# WiFi_RGB_Lights.net
KiCad netlist of a schematic drawn in EAGLE
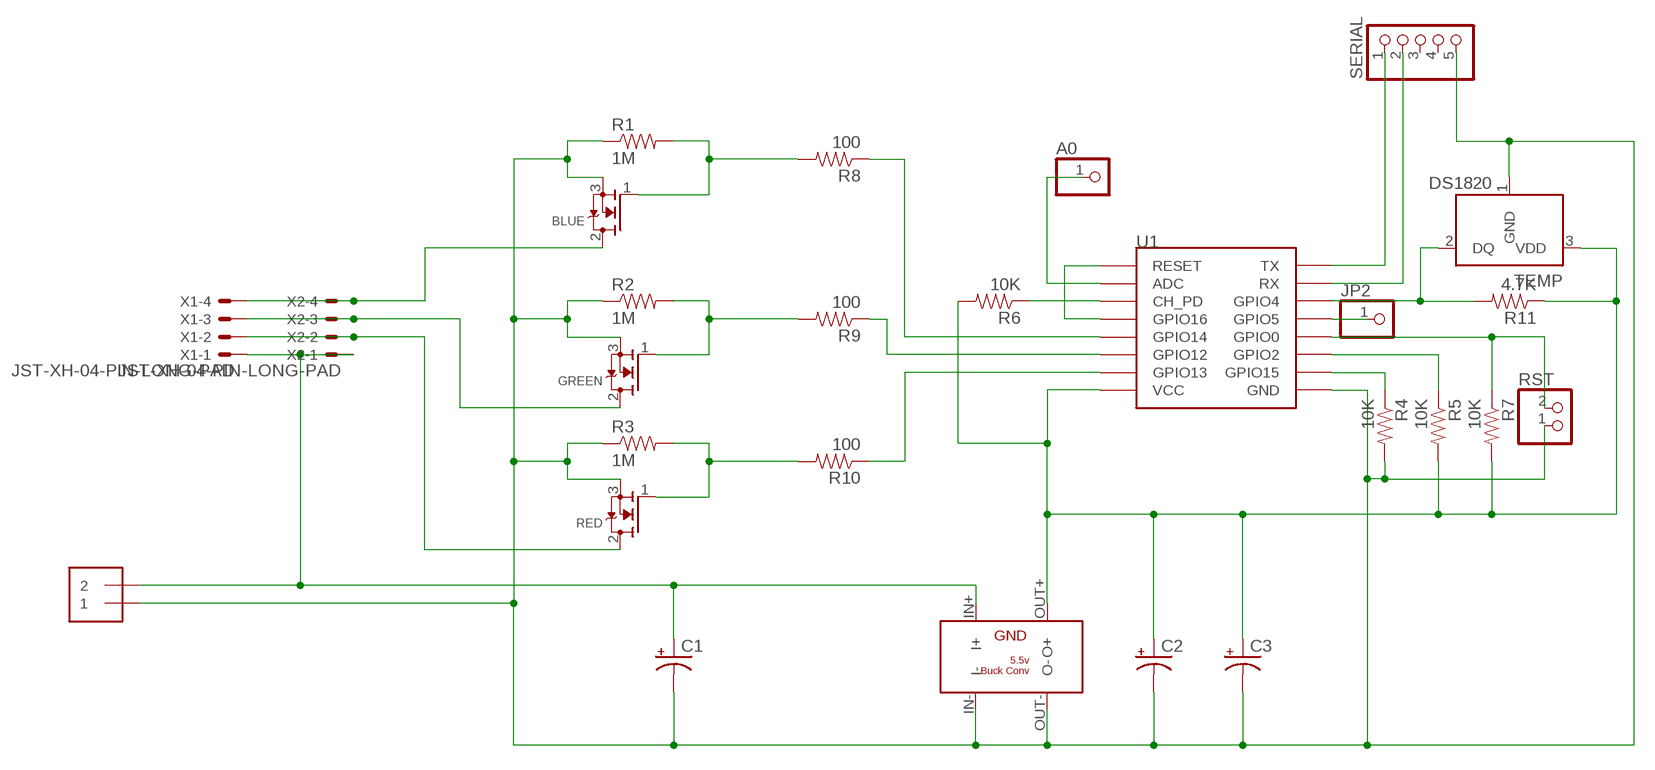
[diagram p0: schematic, sheet 1]

(export (version "E")
  (design (tool "Eeschema 10.0.6"))
  (components
    (comp (ref "3.3V")
      (value "BUCK_CONV_5.5V")
      (footprint "eagle-import:BUCK_CONV")
      (libsource (lib "eagle-import") (part "BUCK_CONV_5.5V"))
    )
    (comp (ref "A0")
      (value "PINHD-1X1")
      (footprint "eagle-import:1X01")
      (libsource (lib "eagle-import") (part "PINHD-1X1"))
    )
    (comp (ref "BLUE")
      (value "MOSFET-NGDS_TO220V")
      (footprint "eagle-import:TO220V")
      (libsource (lib "eagle-import") (part "MOSFET-NGDS_TO220V"))
    )
    (comp (ref "C1")
      (value "CPOL-USE5-8.5")
      (footprint "eagle-import:E5-8,5")
      (libsource (lib "eagle-import") (part "CPOL-USE5-8.5"))
    )
    (comp (ref "C2")
      (value "CPOL-USE2.5-6")
      (footprint "eagle-import:E2,5-6")
      (libsource (lib "eagle-import") (part "CPOL-USE2.5-6"))
    )
    (comp (ref "C3")
      (value "CPOL-USE2.5-6")
      (footprint "eagle-import:E2,5-6")
      (libsource (lib "eagle-import") (part "CPOL-USE2.5-6"))
    )
    (comp (ref "GREEN")
      (value "MOSFET-NGDS_TO220V")
      (footprint "eagle-import:TO220V")
      (libsource (lib "eagle-import") (part "MOSFET-NGDS_TO220V"))
    )
    (comp (ref "JP2")
      (value "PINHD-1X1")
      (footprint "eagle-import:1X01")
      (libsource (lib "eagle-import") (part "PINHD-1X1"))
    )
    (comp (ref "PWR")
      (value "5MM_TERMINAL_BLOCK")
      (footprint "eagle-import:5MM_TERMINAL_BLOCK")
      (libsource (lib "eagle-import") (part "5MM_TERMINAL_BLOCK"))
    )
    (comp (ref "R1")
      (value "1M")
      (footprint "eagle-import:1206")
      (libsource (lib "eagle-import") (part "RESISTOR1206"))
    )
    (comp (ref "R2")
      (value "1M")
      (footprint "eagle-import:1206")
      (libsource (lib "eagle-import") (part "RESISTOR1206"))
    )
    (comp (ref "R3")
      (value "1M")
      (footprint "eagle-import:1206")
      (libsource (lib "eagle-import") (part "RESISTOR1206"))
    )
    (comp (ref "R4")
      (value "10K")
      (footprint "eagle-import:1206")
      (libsource (lib "eagle-import") (part "RESISTOR1206"))
    )
    (comp (ref "R5")
      (value "10K")
      (footprint "eagle-import:1206")
      (libsource (lib "eagle-import") (part "RESISTOR1206"))
    )
    (comp (ref "R6")
      (value "10K")
      (footprint "eagle-import:1206")
      (libsource (lib "eagle-import") (part "RESISTOR1206"))
    )
    (comp (ref "R7")
      (value "10K")
      (footprint "eagle-import:1206")
      (libsource (lib "eagle-import") (part "RESISTOR1206"))
    )
    (comp (ref "R8")
      (value "100")
      (footprint "eagle-import:0805")
      (libsource (lib "eagle-import") (part "RESISTOR0805-RES"))
    )
    (comp (ref "R9")
      (value "100")
      (footprint "eagle-import:0805")
      (libsource (lib "eagle-import") (part "RESISTOR0805-RES"))
    )
    (comp (ref "R10")
      (value "100")
      (footprint "eagle-import:0805")
      (libsource (lib "eagle-import") (part "RESISTOR0805-RES"))
    )
    (comp (ref "R11")
      (value "4.7K")
      (footprint "eagle-import:1206")
      (libsource (lib "eagle-import") (part "RESISTOR1206"))
    )
    (comp (ref "RED")
      (value "MOSFET-NGDS_TO220V")
      (footprint "eagle-import:TO220V")
      (libsource (lib "eagle-import") (part "MOSFET-NGDS_TO220V"))
    )
    (comp (ref "RST")
      (value "JST_2PIN-THM")
      (footprint "eagle-import:JST-PH-2-THM")
      (libsource (lib "eagle-import") (part "JST_2PIN-THM"))
    )
    (comp (ref "SERIAL")
      (value "PINHD-1X5")
      (footprint "eagle-import:1X05")
      (libsource (lib "eagle-import") (part "PINHD-1X5"))
    )
    (comp (ref "TEMP")
      (value "DS1820")
      (footprint "eagle-import:TO-92")
      (libsource (lib "eagle-import") (part "DS1820"))
    )
    (comp (ref "U1")
      (value "ESP12")
      (footprint "eagle-import:ESP12")
      (libsource (lib "eagle-import") (part "ESP12"))
    )
    (comp (ref "X1")
      (value "JST-XH-04-PIN-LONG-PAD")
      (footprint "eagle-import:JST-XH-04-PACKAGE-LONG-PAD")
      (libsource (lib "eagle-import") (part "JST-XH-04-PIN-LONG-PAD"))
    )
    (comp (ref "X2")
      (value "JST-XH-04-PIN-LONG-PAD")
      (footprint "eagle-import:JST-XH-04-PACKAGE-LONG-PAD")
      (libsource (lib "eagle-import") (part "JST-XH-04-PIN-LONG-PAD"))
    )
  )
  (nets
    (net (code "1") (name "Net-(3.3V-I+)") (class "Default")
      (node (ref "3.3V") (pin "IN+") (pinfunction "I+_IN+") (pintype "bidirectional"))
      (node (ref "C1") (pin "+") (pinfunction "+_+") (pintype "passive"))
      (node (ref "PWR") (pin "2") (pinfunction "2_2") (pintype "passive"))
      (node (ref "X1") (pin "1") (pinfunction "S_1") (pintype "passive"))
      (node (ref "X2") (pin "1") (pinfunction "S_1") (pintype "passive"))
    )
    (net (code "2") (name "Net-(3.3V-I-)") (class "Default")
      (node (ref "3.3V") (pin "IN-") (pinfunction "I-_IN-") (pintype "bidirectional"))
      (node (ref "3.3V") (pin "OUT-") (pinfunction "O-_OUT-") (pintype "bidirectional"))
      (node (ref "BLUE") (pin "3") (pinfunction "S_3") (pintype "bidirectional"))
      (node (ref "C1") (pin "-") (pinfunction "-_-") (pintype "passive"))
      (node (ref "C2") (pin "-") (pinfunction "-_-") (pintype "passive"))
      (node (ref "C3") (pin "-") (pinfunction "-_-") (pintype "passive"))
      (node (ref "GREEN") (pin "3") (pinfunction "S_3") (pintype "bidirectional"))
      (node (ref "PWR") (pin "1") (pinfunction "1_1") (pintype "passive"))
      (node (ref "R1") (pin "1") (pinfunction "1_1") (pintype "passive"))
      (node (ref "R2") (pin "1") (pinfunction "1_1") (pintype "passive"))
      (node (ref "R3") (pin "1") (pinfunction "1_1") (pintype "passive"))
      (node (ref "R4") (pin "2") (pinfunction "2_2") (pintype "passive"))
      (node (ref "RED") (pin "3") (pinfunction "S_3") (pintype "bidirectional"))
      (node (ref "RST") (pin "1") (pinfunction "2_1") (pintype "passive"))
      (node (ref "SERIAL") (pin "5") (pinfunction "5_5") (pintype "passive"))
      (node (ref "TEMP") (pin "1") (pinfunction "GND_1") (pintype "power_in"))
      (node (ref "U1") (pin "GND") (pinfunction "GND_GND") (pintype "bidirectional"))
    )
    (net (code "3") (name "Net-(3.3V-O+)") (class "Default")
      (node (ref "3.3V") (pin "OUT+") (pinfunction "O+_OUT+") (pintype "bidirectional"))
      (node (ref "C2") (pin "+") (pinfunction "+_+") (pintype "passive"))
      (node (ref "C3") (pin "+") (pinfunction "+_+") (pintype "passive"))
      (node (ref "R11") (pin "1") (pinfunction "1_1") (pintype "passive"))
      (node (ref "R5") (pin "2") (pinfunction "2_2") (pintype "passive"))
      (node (ref "R6") (pin "2") (pinfunction "2_2") (pintype "passive"))
      (node (ref "R7") (pin "2") (pinfunction "2_2") (pintype "passive"))
      (node (ref "TEMP") (pin "3") (pinfunction "VDD_3") (pintype "input"))
      (node (ref "U1") (pin "VCC") (pinfunction "VCC_VCC") (pintype "bidirectional"))
    )
    (net (code "4") (name "Net-(A0-Pad1)") (class "Default")
      (node (ref "A0") (pin "1") (pinfunction "1_1") (pintype "passive"))
      (node (ref "U1") (pin "ADC") (pinfunction "ADC_ADC") (pintype "bidirectional"))
    )
    (net (code "5") (name "Net-(BLUE-D)") (class "Default")
      (node (ref "BLUE") (pin "2") (pinfunction "D_2") (pintype "bidirectional"))
      (node (ref "X1") (pin "4") (pinfunction "S_4") (pintype "passive"))
      (node (ref "X2") (pin "4") (pinfunction "S_4") (pintype "passive"))
    )
    (net (code "6") (name "Net-(BLUE-G)") (class "Default")
      (node (ref "BLUE") (pin "1") (pinfunction "G_1") (pintype "bidirectional"))
      (node (ref "R1") (pin "2") (pinfunction "2_2") (pintype "passive"))
      (node (ref "R8") (pin "2") (pinfunction "2_2") (pintype "passive"))
    )
    (net (code "7") (name "Net-(GREEN-D)") (class "Default")
      (node (ref "GREEN") (pin "2") (pinfunction "D_2") (pintype "bidirectional"))
      (node (ref "X1") (pin "3") (pinfunction "S_3") (pintype "passive"))
      (node (ref "X2") (pin "3") (pinfunction "S_3") (pintype "passive"))
    )
    (net (code "8") (name "Net-(GREEN-G)") (class "Default")
      (node (ref "GREEN") (pin "1") (pinfunction "G_1") (pintype "bidirectional"))
      (node (ref "R2") (pin "2") (pinfunction "2_2") (pintype "passive"))
      (node (ref "R9") (pin "2") (pinfunction "2_2") (pintype "passive"))
    )
    (net (code "9") (name "Net-(JP2-Pad1)") (class "Default")
      (node (ref "JP2") (pin "1") (pinfunction "1_1") (pintype "passive"))
      (node (ref "U1") (pin "GPIO5") (pinfunction "GPIO5_GPIO5") (pintype "bidirectional"))
    )
    (net (code "10") (name "Net-(R4-Pad1)") (class "Default")
      (node (ref "R4") (pin "1") (pinfunction "1_1") (pintype "passive"))
      (node (ref "U1") (pin "GPIO15") (pinfunction "GPIO15_GPIO15") (pintype "bidirectional"))
    )
    (net (code "11") (name "Net-(R5-Pad1)") (class "Default")
      (node (ref "R5") (pin "1") (pinfunction "1_1") (pintype "passive"))
      (node (ref "U1") (pin "GPIO2") (pinfunction "GPIO2_GPIO2") (pintype "bidirectional"))
    )
    (net (code "12") (name "Net-(R6-Pad1)") (class "Default")
      (node (ref "R6") (pin "1") (pinfunction "1_1") (pintype "passive"))
      (node (ref "U1") (pin "CH_PD") (pinfunction "CH_PD_CH_PD") (pintype "bidirectional"))
    )
    (net (code "13") (name "Net-(R8-Pad1)") (class "Default")
      (node (ref "R8") (pin "1") (pinfunction "1_1") (pintype "passive"))
      (node (ref "U1") (pin "GPIO14") (pinfunction "GPIO14_GPIO14") (pintype "bidirectional"))
    )
    (net (code "14") (name "Net-(R9-Pad1)") (class "Default")
      (node (ref "R9") (pin "1") (pinfunction "1_1") (pintype "passive"))
      (node (ref "U1") (pin "GPIO12") (pinfunction "GPIO12_GPIO12") (pintype "bidirectional"))
    )
    (net (code "15") (name "Net-(R10-Pad1)") (class "Default")
      (node (ref "R10") (pin "1") (pinfunction "1_1") (pintype "passive"))
      (node (ref "U1") (pin "GPIO13") (pinfunction "GPIO13_GPIO13") (pintype "bidirectional"))
    )
    (net (code "16") (name "Net-(RED-D)") (class "Default")
      (node (ref "RED") (pin "2") (pinfunction "D_2") (pintype "bidirectional"))
      (node (ref "X1") (pin "2") (pinfunction "S_2") (pintype "passive"))
      (node (ref "X2") (pin "2") (pinfunction "S_2") (pintype "passive"))
    )
    (net (code "17") (name "Net-(RED-G)") (class "Default")
      (node (ref "R10") (pin "2") (pinfunction "2_2") (pintype "passive"))
      (node (ref "R3") (pin "2") (pinfunction "2_2") (pintype "passive"))
      (node (ref "RED") (pin "1") (pinfunction "G_1") (pintype "bidirectional"))
    )
    (net (code "18") (name "Net-(RST-1)") (class "Default")
      (node (ref "R7") (pin "1") (pinfunction "1_1") (pintype "passive"))
      (node (ref "RST") (pin "2") (pinfunction "1_2") (pintype "passive"))
      (node (ref "U1") (pin "GPIO0") (pinfunction "GPIO0_GPIO0") (pintype "bidirectional"))
    )
    (net (code "19") (name "Net-(SERIAL-Pad1)") (class "Default")
      (node (ref "SERIAL") (pin "1") (pinfunction "1_1") (pintype "passive"))
      (node (ref "U1") (pin "TX") (pinfunction "TX_TX") (pintype "bidirectional"))
    )
    (net (code "20") (name "Net-(SERIAL-Pad2)") (class "Default")
      (node (ref "SERIAL") (pin "2") (pinfunction "2_2") (pintype "passive"))
      (node (ref "U1") (pin "RX") (pinfunction "RX_RX") (pintype "bidirectional"))
    )
    (net (code "21") (name "Net-(TEMP-DQ)") (class "Default")
      (node (ref "R11") (pin "2") (pinfunction "2_2") (pintype "passive"))
      (node (ref "TEMP") (pin "2") (pinfunction "DQ_2") (pintype "output"))
      (node (ref "U1") (pin "GPIO4") (pinfunction "GPIO4_GPIO4") (pintype "bidirectional"))
    )
    (net (code "22") (name "Net-(U1-PadGPIO16)") (class "Default")
      (node (ref "U1") (pin "GPIO16") (pinfunction "GPIO16_GPIO16") (pintype "bidirectional"))
      (node (ref "U1") (pin "RESET") (pinfunction "RESET_RESET") (pintype "bidirectional"))
    )
    (net (code "23") (name "unconnected-(SERIAL-Pad3)") (class "Default")
      (node (ref "SERIAL") (pin "3") (pinfunction "3_3") (pintype "passive"))
    )
    (net (code "24") (name "unconnected-(SERIAL-Pad4)") (class "Default")
      (node (ref "SERIAL") (pin "4") (pinfunction "4_4") (pintype "passive"))
    )
  )
)
